# ProPrj__-8777947A-__2025-12-19.net
KiCad netlist of a schematic drawn in EasyEDA Pro
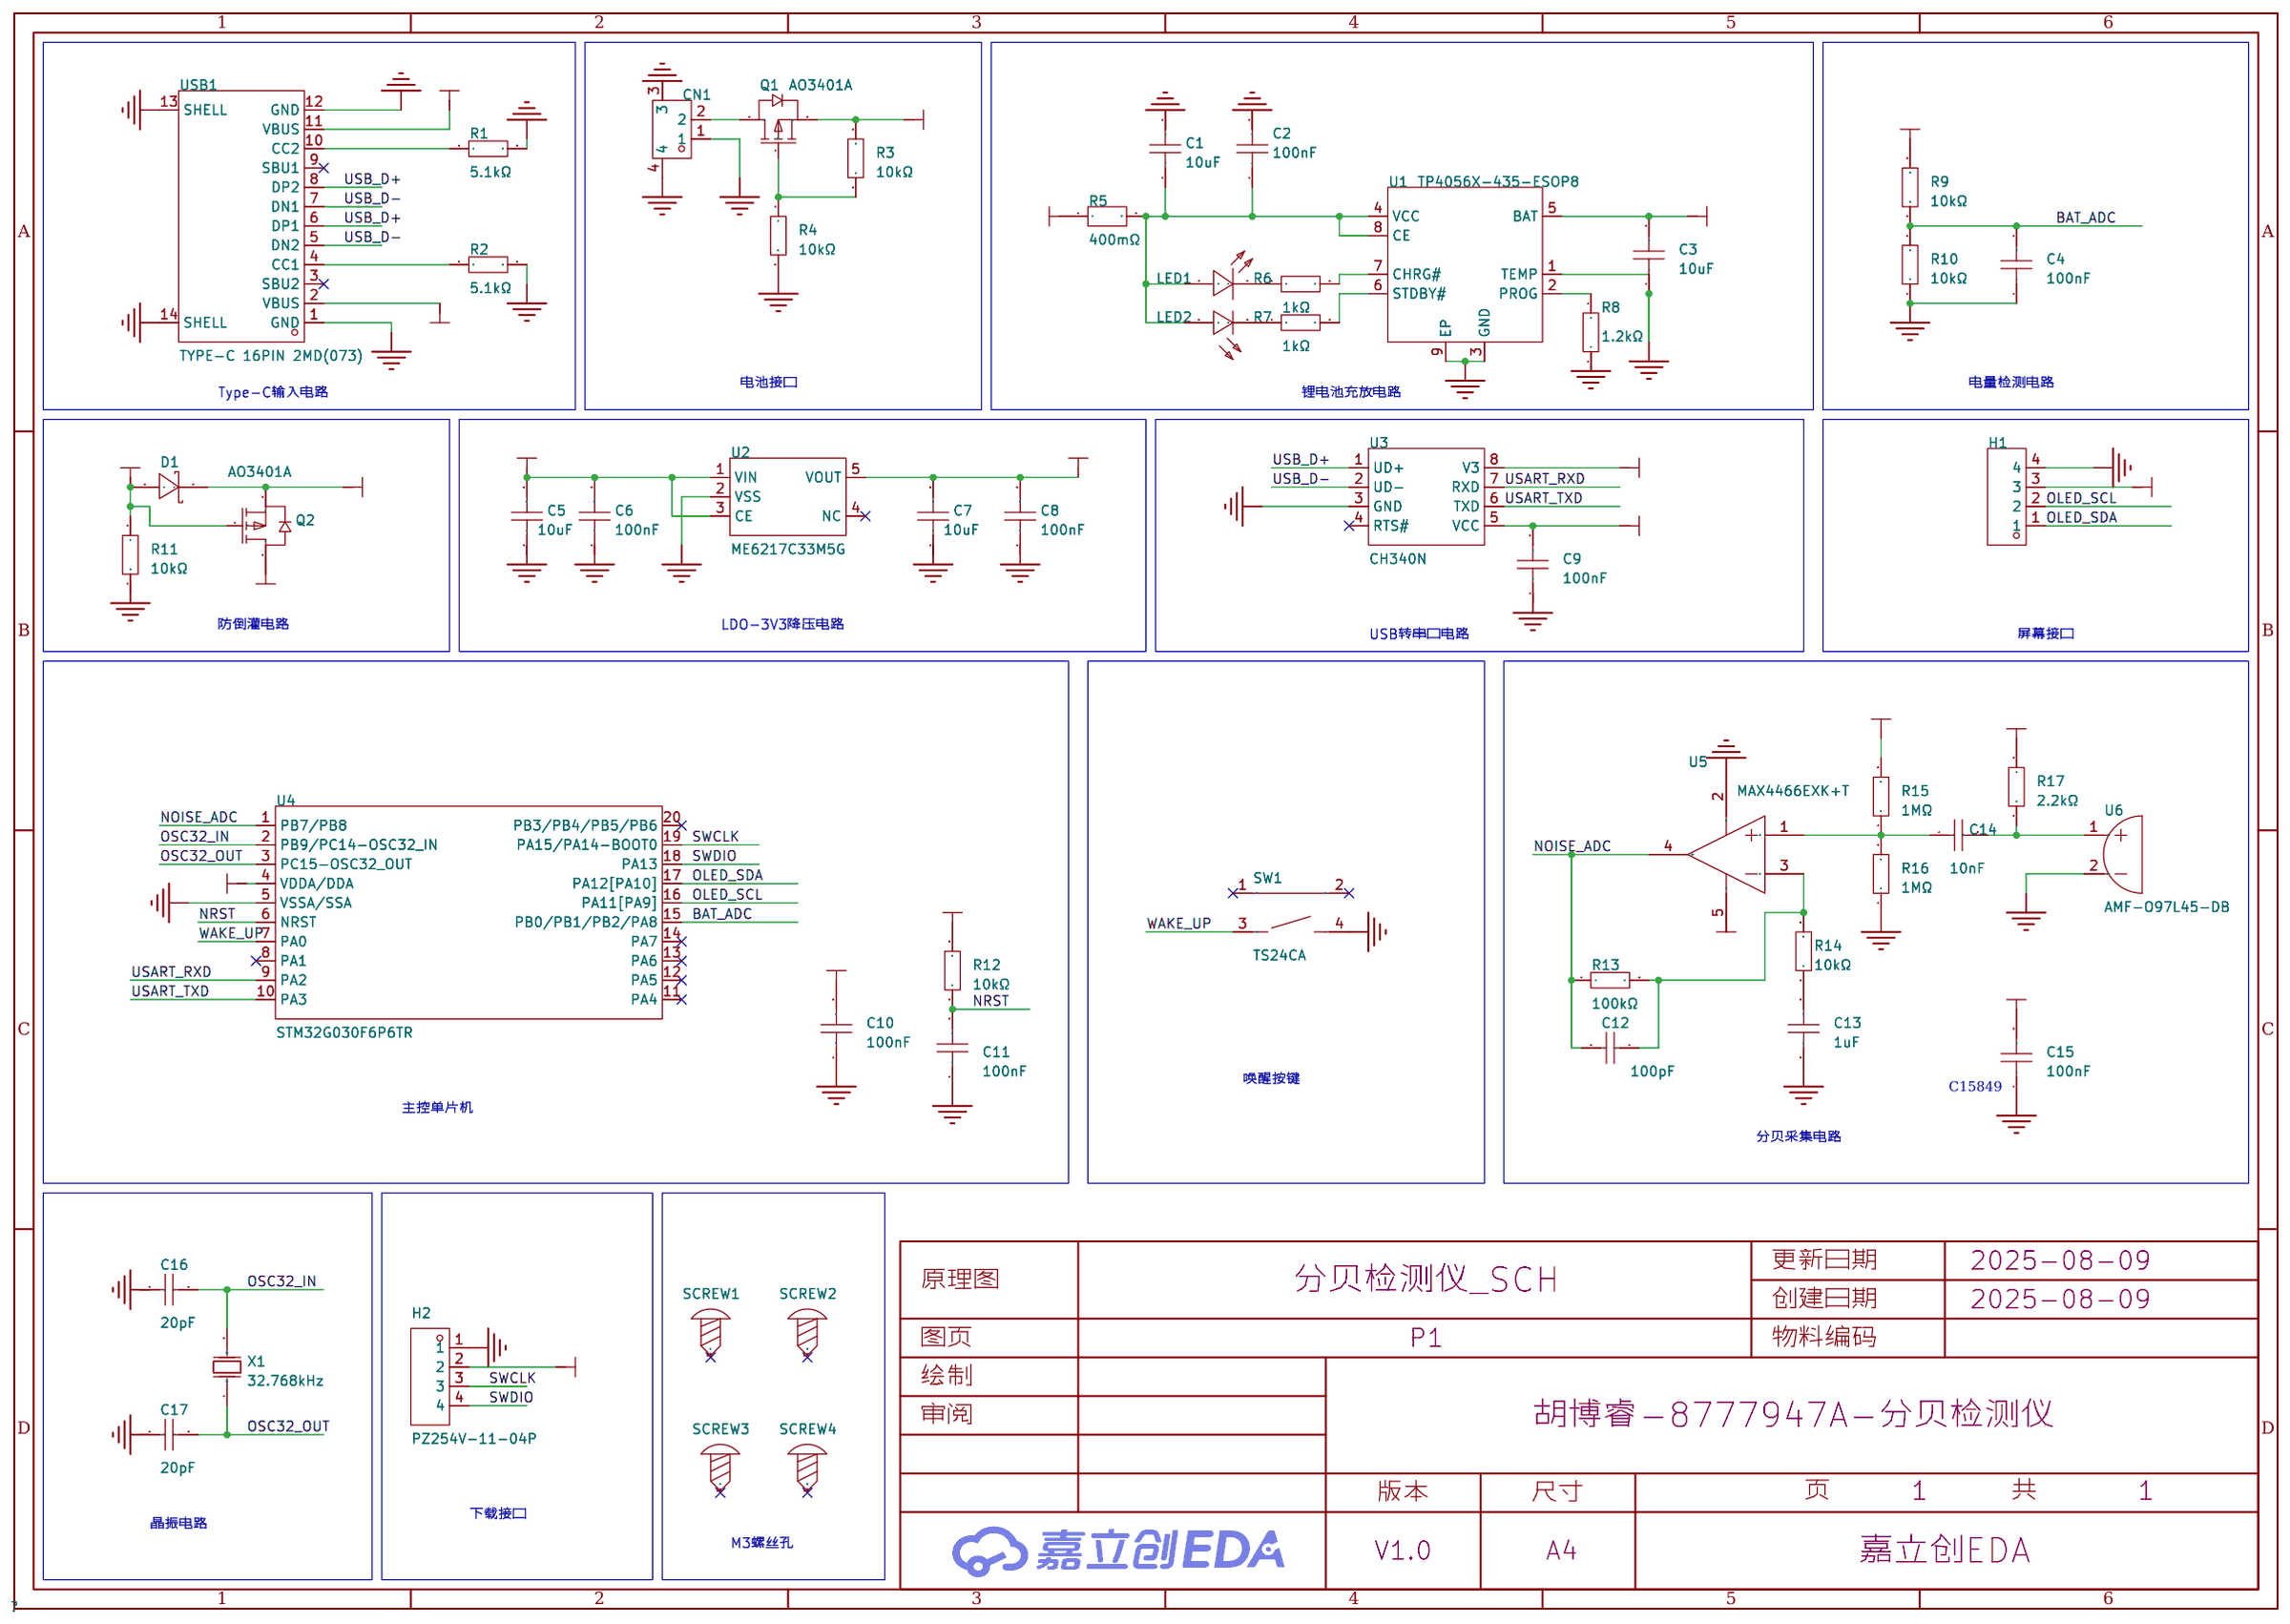
[diagram p0: schematic sheet]

(export (version "E")
  (design (tool "Eeschema 10.0.6"))
  (components
    (comp (ref "C1")
      (value "10uF")
      (footprint "easyedapro:C0805")
      (description "容值:10uF;精度:±10%;额定电压:25V;材质(温度系数):X5R;")
      (fields
        (field (name "Manufacturer Part") "CL21A106KAYNNNE")
        (field (name "Manufacturer") "SAMSUNG(三星)")
      )
      (libsource (lib "easyedapro") (part "CL21A106KAYNNNE"))
    )
    (comp (ref "C2")
      (value "100nF")
      (footprint "easyedapro:C0603")
      (description "容值:100nF;精度:±10%;额定电压:50V;温度系数:X7R;")
      (fields
        (field (name "Manufacturer Part") "CC0603KRX7R9BB104")
        (field (name "Manufacturer") "YAGEO(国巨)")
      )
      (libsource (lib "easyedapro") (part "CC0603KRX7R9BB104"))
    )
    (comp (ref "C3")
      (value "10uF")
      (footprint "easyedapro:C0805")
      (description "容值:10uF;精度:±10%;额定电压:25V;材质(温度系数):X5R;")
      (fields
        (field (name "Manufacturer Part") "CL21A106KAYNNNE")
        (field (name "Manufacturer") "SAMSUNG(三星)")
      )
      (libsource (lib "easyedapro") (part "CL21A106KAYNNNE"))
    )
    (comp (ref "C4")
      (value "100nF")
      (footprint "easyedapro:C0603")
      (description "容值:100nF;精度:±10%;额定电压:50V;温度系数:X7R;")
      (fields
        (field (name "Manufacturer Part") "CC0603KRX7R9BB104")
        (field (name "Manufacturer") "YAGEO(国巨)")
      )
      (libsource (lib "easyedapro") (part "CC0603KRX7R9BB104"))
    )
    (comp (ref "C5")
      (value "10uF")
      (footprint "easyedapro:C0805")
      (description "容值:10uF;精度:±10%;额定电压:25V;材质(温度系数):X5R;")
      (fields
        (field (name "Manufacturer Part") "CL21A106KAYNNNE")
        (field (name "Manufacturer") "SAMSUNG(三星)")
      )
      (libsource (lib "easyedapro") (part "CL21A106KAYNNNE"))
    )
    (comp (ref "C6")
      (value "100nF")
      (footprint "easyedapro:C0603")
      (description "容值:100nF;精度:±10%;额定电压:50V;温度系数:X7R;")
      (fields
        (field (name "Manufacturer Part") "CC0603KRX7R9BB104")
        (field (name "Manufacturer") "YAGEO(国巨)")
      )
      (libsource (lib "easyedapro") (part "CC0603KRX7R9BB104"))
    )
    (comp (ref "C7")
      (value "10uF")
      (footprint "easyedapro:C0805")
      (description "容值:10uF;精度:±10%;额定电压:25V;材质(温度系数):X5R;")
      (fields
        (field (name "Manufacturer Part") "CL21A106KAYNNNE")
        (field (name "Manufacturer") "SAMSUNG(三星)")
      )
      (libsource (lib "easyedapro") (part "CL21A106KAYNNNE"))
    )
    (comp (ref "C8")
      (value "100nF")
      (footprint "easyedapro:C0603")
      (description "容值:100nF;精度:±10%;额定电压:50V;温度系数:X7R;")
      (fields
        (field (name "Manufacturer Part") "CC0603KRX7R9BB104")
        (field (name "Manufacturer") "YAGEO(国巨)")
      )
      (libsource (lib "easyedapro") (part "CC0603KRX7R9BB104"))
    )
    (comp (ref "C9")
      (value "100nF")
      (footprint "easyedapro:C0603")
      (description "容值:100nF;精度:±10%;额定电压:50V;温度系数:X7R;")
      (fields
        (field (name "Manufacturer Part") "CC0603KRX7R9BB104")
        (field (name "Manufacturer") "YAGEO(国巨)")
      )
      (libsource (lib "easyedapro") (part "CC0603KRX7R9BB104"))
    )
    (comp (ref "C10")
      (value "100nF")
      (footprint "easyedapro:C0603")
      (description "容值:100nF;精度:±10%;额定电压:50V;温度系数:X7R;")
      (fields
        (field (name "Manufacturer Part") "CC0603KRX7R9BB104")
        (field (name "Manufacturer") "YAGEO(国巨)")
      )
      (libsource (lib "easyedapro") (part "CC0603KRX7R9BB104"))
    )
    (comp (ref "C11")
      (value "100nF")
      (footprint "easyedapro:C0603")
      (description "容值:100nF;精度:±10%;额定电压:50V;温度系数:X7R;")
      (fields
        (field (name "Manufacturer Part") "CC0603KRX7R9BB104")
        (field (name "Manufacturer") "YAGEO(国巨)")
      )
      (libsource (lib "easyedapro") (part "CC0603KRX7R9BB104"))
    )
    (comp (ref "C12")
      (value "100pF")
      (footprint "easyedapro:C0603")
      (description "容值:100pF;精度:±5%;额定电压:50V;材质(温度系数):C0G;")
      (fields
        (field (name "Manufacturer Part") "CL10C101JB8NNNC")
        (field (name "Manufacturer") "SAMSUNG(三星)")
      )
      (libsource (lib "easyedapro") (part "CL10C101JB8NNNC"))
    )
    (comp (ref "C13")
      (value "1uF")
      (footprint "easyedapro:C0603")
      (description "容值:1uF;精度:±10%;额定电压:50V;材质(温度系数):X5R;")
      (fields
        (field (name "Manufacturer Part") "CL10A105KB8NNNC")
        (field (name "Manufacturer") "SAMSUNG(三星)")
      )
      (libsource (lib "easyedapro") (part "CL10A105KB8NNNC"))
    )
    (comp (ref "C14")
      (value "10nF")
      (footprint "easyedapro:C0603")
      (description "容值:10nF;精度:±10%;额定电压:50V;温度系数:X7R;")
      (fields (field (name "Manufacturer Part") "0603B103K500NT") (field (name "Manufacturer") "FH(风华)"))
      (libsource (lib "easyedapro") (part "0603B103K500NT"))
    )
    (comp (ref "C15")
      (value "100nF")
      (footprint "easyedapro:C0603")
      (description "容值:100nF;精度:±10%;额定电压:50V;温度系数:X7R;")
      (fields
        (field (name "Manufacturer Part") "CC0603KRX7R9BB104")
        (field (name "Manufacturer") "YAGEO(国巨)")
      )
      (libsource (lib "easyedapro") (part "CC0603KRX7R9BB104"))
    )
    (comp (ref "C16")
      (value "20pF")
      (footprint "easyedapro:C0603")
      (description "容值:20pF;精度:±5%;额定电压:50V;材质(温度系数):C0G;")
      (fields
        (field (name "Manufacturer Part") "CL10C200JB8NNNC")
        (field (name "Manufacturer") "SAMSUNG(三星)")
      )
      (libsource (lib "easyedapro") (part "CL10C200JB8NNNC"))
    )
    (comp (ref "C17")
      (value "20pF")
      (footprint "easyedapro:C0603")
      (description "容值:20pF;精度:±5%;额定电压:50V;材质(温度系数):C0G;")
      (fields
        (field (name "Manufacturer Part") "CL10C200JB8NNNC")
        (field (name "Manufacturer") "SAMSUNG(三星)")
      )
      (libsource (lib "easyedapro") (part "CL10C200JB8NNNC"))
    )
    (comp (ref "CN1")
      (value "WAFER-254W-2A")
      (footprint "easyedapro:CONN-SMD_2P-L10.0-W7.8-P2.5")
      (description "插针结构:1x2P;间距:2.54mm;安装方式:卧贴;参考系列:XH;总PIN数:2P;排数:1;每排PIN数:2;行距:-;额定电流:3A;工作温度:-25°C~+85°C;")
      (fields (field (name "Manufacturer") "HANBO(汉博)"))
      (libsource (lib "easyedapro") (part "WAFER-254W-2A"))
    )
    (comp (ref "D1")
      (value "1N5819WS")
      (footprint "easyedapro:SOD-323_L1.8-W1.3-LS2.5-RD")
      (description "正向压降(Vf):600mV@1A;直流反向耐压(Vr):40V;整流电流:1A;")
      (fields (field (name "Manufacturer") "Hottech(合科泰)"))
      (libsource (lib "easyedapro") (part "1N5819WS"))
    )
    (comp (ref "H1")
      (value "2.54-1*4P母")
      (footprint "easyedapro:HDR-TH_4P-P2.54-V-F")
      (fields (field (name "Manufacturer") "BOOMELE(博穆精密)"))
      (libsource (lib "easyedapro") (part "2.54-1*4P母"))
    )
    (comp (ref "H2")
      (value "PZ254V-11-04P")
      (footprint "easyedapro:HDR-TH_4P-P2.54-V-M")
      (fields (field (name "Manufacturer") "XFCN(兴飞)"))
      (libsource (lib "easyedapro") (part "PZ254V-11-04P_C2691448"))
    )
    (comp (ref "LED1")
      (value "KT-0603R")
      (footprint "easyedapro:LED0603-RD")
      (description "发光颜色:红色;功率:-;正向电流:-;主波长:-;二极管配置:-;透镜颜色:-;色温:-;发光角度:-;载带方式:-;工作温度:-40°C~+85°C;")
      (fields (field (name "Manufacturer") "KENTO"))
      (libsource (lib "easyedapro") (part "KT-0603R"))
    )
    (comp (ref "LED2")
      (value "NCD0603G1")
      (footprint "easyedapro:LED0603-RD_1")
      (fields (field (name "Manufacturer") "国星光电"))
      (libsource (lib "easyedapro") (part "FC-D1608UGK-520D10"))
    )
    (comp (ref "Q1")
      (value "AO3401A")
      (footprint "easyedapro:SOT-23_L2.9-W1.3-P1.90-LS2.4-BR")
      (fields (field (name "Manufacturer") "UMW(友台半导体)"))
      (libsource (lib "easyedapro") (part "AO3401A_C347476"))
    )
    (comp (ref "Q2")
      (value "AO3401A")
      (footprint "easyedapro:SOT-23_L2.9-W1.3-P1.90-LS2.4-BR")
      (fields (field (name "Manufacturer") "UMW(友台半导体)"))
      (libsource (lib "easyedapro") (part "AO3401A_C347476"))
    )
    (comp (ref "R1")
      (value "5.1kΩ")
      (footprint "easyedapro:R0603")
      (description "电阻类型:厚膜电阻;阻值:5.1kΩ;精度:±1%;功率:100mW;工作电压:75V;温度系数:±100ppm/°C;")
      (fields
        (field (name "Manufacturer Part") "0603WAF5101T5E")
        (field (name "Manufacturer") "UNI-ROYAL(厚声)")
      )
      (libsource (lib "easyedapro") (part "0603WAF5101T5E"))
    )
    (comp (ref "R2")
      (value "5.1kΩ")
      (footprint "easyedapro:R0603")
      (description "电阻类型:厚膜电阻;阻值:5.1kΩ;精度:±1%;功率:100mW;工作电压:75V;温度系数:±100ppm/°C;")
      (fields
        (field (name "Manufacturer Part") "0603WAF5101T5E")
        (field (name "Manufacturer") "UNI-ROYAL(厚声)")
      )
      (libsource (lib "easyedapro") (part "0603WAF5101T5E"))
    )
    (comp (ref "R3")
      (value "10kΩ")
      (footprint "easyedapro:R0603")
      (description "电阻类型:厚膜电阻;阻值:10kΩ;精度:±1%;功率:100mW;工作电压:75V;温度系数:±100ppm/°C;")
      (fields
        (field (name "Manufacturer Part") "0603WAF1002T5E")
        (field (name "Manufacturer") "UNI-ROYAL(厚声)")
      )
      (libsource (lib "easyedapro") (part "0603WAF1002T5E"))
    )
    (comp (ref "R4")
      (value "10kΩ")
      (footprint "easyedapro:R0603")
      (description "电阻类型:厚膜电阻;阻值:10kΩ;精度:±1%;功率:100mW;工作电压:75V;温度系数:±100ppm/°C;")
      (fields
        (field (name "Manufacturer Part") "0603WAF1002T5E")
        (field (name "Manufacturer") "UNI-ROYAL(厚声)")
      )
      (libsource (lib "easyedapro") (part "0603WAF1002T5E"))
    )
    (comp (ref "R5")
      (value "400mΩ")
      (footprint "easyedapro:R1206")
      (description "电阻类型:厚膜电阻;阻值:400mΩ;精度:±1%;功率:250mW;最大工作电压:500V;温度系数:±300ppm/°C;")
      (fields (field (name "Manufacturer Part") "FRL1206FR400TS") (field (name "Manufacturer") "FOJAN(富捷)"))
      (libsource (lib "easyedapro") (part "FRL1206FR400TS"))
    )
    (comp (ref "R6")
      (value "1kΩ")
      (footprint "easyedapro:R0603")
      (description "电阻类型:厚膜电阻;阻值:1kΩ;精度:±1%;功率:100mW;最大工作电压:75V;温度系数:±100ppm/°C;")
      (fields
        (field (name "Manufacturer Part") "0603WAF1001T5E")
        (field (name "Manufacturer") "UNI-ROYAL(厚声)")
      )
      (libsource (lib "easyedapro") (part "0603WAF1001T5E"))
    )
    (comp (ref "R7")
      (value "1kΩ")
      (footprint "easyedapro:R0603")
      (description "电阻类型:厚膜电阻;阻值:1kΩ;精度:±1%;功率:100mW;最大工作电压:75V;温度系数:±100ppm/°C;")
      (fields
        (field (name "Manufacturer Part") "0603WAF1001T5E")
        (field (name "Manufacturer") "UNI-ROYAL(厚声)")
      )
      (libsource (lib "easyedapro") (part "0603WAF1001T5E"))
    )
    (comp (ref "R8")
      (value "1.2kΩ")
      (footprint "easyedapro:R0603")
      (description "电阻类型:厚膜电阻;阻值:1.2kΩ;精度:±1%;功率:100mW;最大工作电压:75V;温度系数:±100ppm/°C;")
      (fields
        (field (name "Manufacturer Part") "0603WAF1201T5E")
        (field (name "Manufacturer") "UNI-ROYAL(厚声)")
      )
      (libsource (lib "easyedapro") (part "0603WAF1201T5E"))
    )
    (comp (ref "R9")
      (value "10kΩ")
      (footprint "easyedapro:R0603")
      (description "电阻类型:厚膜电阻;阻值:10kΩ;精度:±1%;功率:100mW;工作电压:75V;温度系数:±100ppm/°C;")
      (fields
        (field (name "Manufacturer Part") "0603WAF1002T5E")
        (field (name "Manufacturer") "UNI-ROYAL(厚声)")
      )
      (libsource (lib "easyedapro") (part "0603WAF1002T5E"))
    )
    (comp (ref "R10")
      (value "10kΩ")
      (footprint "easyedapro:R0603")
      (description "电阻类型:厚膜电阻;阻值:10kΩ;精度:±1%;功率:100mW;工作电压:75V;温度系数:±100ppm/°C;")
      (fields
        (field (name "Manufacturer Part") "0603WAF1002T5E")
        (field (name "Manufacturer") "UNI-ROYAL(厚声)")
      )
      (libsource (lib "easyedapro") (part "0603WAF1002T5E"))
    )
    (comp (ref "R11")
      (value "10kΩ")
      (footprint "easyedapro:R0603")
      (description "电阻类型:厚膜电阻;阻值:10kΩ;精度:±1%;功率:100mW;工作电压:75V;温度系数:±100ppm/°C;")
      (fields
        (field (name "Manufacturer Part") "0603WAF1002T5E")
        (field (name "Manufacturer") "UNI-ROYAL(厚声)")
      )
      (libsource (lib "easyedapro") (part "0603WAF1002T5E"))
    )
    (comp (ref "R12")
      (value "10kΩ")
      (footprint "easyedapro:R0603")
      (description "电阻类型:厚膜电阻;阻值:10kΩ;精度:±1%;功率:100mW;工作电压:75V;温度系数:±100ppm/°C;")
      (fields
        (field (name "Manufacturer Part") "0603WAF1002T5E")
        (field (name "Manufacturer") "UNI-ROYAL(厚声)")
      )
      (libsource (lib "easyedapro") (part "0603WAF1002T5E"))
    )
    (comp (ref "R13")
      (value "100kΩ")
      (footprint "easyedapro:R0603")
      (description "电阻类型:厚膜电阻;阻值:100kΩ;精度:±1%;功率:100mW;最大工作电压:75V;温度系数:±100ppm/°C;")
      (fields
        (field (name "Manufacturer Part") "0603WAF1003T5E")
        (field (name "Manufacturer") "UNI-ROYAL(厚声)")
      )
      (libsource (lib "easyedapro") (part "0603WAF1003T5E"))
    )
    (comp (ref "R14")
      (value "10kΩ")
      (footprint "easyedapro:R0603")
      (description "电阻类型:厚膜电阻;阻值:10kΩ;精度:±1%;功率:100mW;工作电压:75V;温度系数:±100ppm/°C;")
      (fields
        (field (name "Manufacturer Part") "0603WAF1002T5E")
        (field (name "Manufacturer") "UNI-ROYAL(厚声)")
      )
      (libsource (lib "easyedapro") (part "0603WAF1002T5E"))
    )
    (comp (ref "R15")
      (value "1MΩ")
      (footprint "easyedapro:R0603")
      (description "电阻类型:厚膜电阻;阻值:1MΩ;精度:±1%;功率:100mW;最大工作电压:75V;温度系数:±100ppm/°C;")
      (fields
        (field (name "Manufacturer Part") "0603WAF1004T5E")
        (field (name "Manufacturer") "UNI-ROYAL(厚声)")
      )
      (libsource (lib "easyedapro") (part "0603WAF1004T5E"))
    )
    (comp (ref "R16")
      (value "1MΩ")
      (footprint "easyedapro:R0603")
      (description "电阻类型:厚膜电阻;阻值:1MΩ;精度:±1%;功率:100mW;最大工作电压:75V;温度系数:±100ppm/°C;")
      (fields
        (field (name "Manufacturer Part") "0603WAF1004T5E")
        (field (name "Manufacturer") "UNI-ROYAL(厚声)")
      )
      (libsource (lib "easyedapro") (part "0603WAF1004T5E"))
    )
    (comp (ref "R17")
      (value "2.2kΩ")
      (footprint "easyedapro:R0603")
      (description "电阻类型:厚膜电阻;阻值:2.2kΩ;精度:±1%;功率:100mW;最大工作电压:75V;温度系数:±100ppm/°C;")
      (fields
        (field (name "Manufacturer Part") "0603WAF2201T5E")
        (field (name "Manufacturer") "UNI-ROYAL(厚声)")
      )
      (libsource (lib "easyedapro") (part "0603WAF2201T5E"))
    )
    (comp (ref "SCREW1")
      (value "~")
      (footprint "easyedapro:M3螺丝")
      (libsource (lib "easyedapro") (part "螺丝孔"))
    )
    (comp (ref "SCREW2")
      (value "~")
      (footprint "easyedapro:M3螺丝")
      (libsource (lib "easyedapro") (part "螺丝孔"))
    )
    (comp (ref "SCREW3")
      (value "~")
      (footprint "easyedapro:M3螺丝")
      (libsource (lib "easyedapro") (part "螺丝孔"))
    )
    (comp (ref "SCREW4")
      (value "~")
      (footprint "easyedapro:M3螺丝")
      (libsource (lib "easyedapro") (part "螺丝孔"))
    )
    (comp (ref "SW1")
      (value "TS24CA")
      (footprint "easyedapro:SW-SMD_TS24CA")
      (description "电路结构:单刀单掷;按钮形状:矩形按钮;安装方式:卧贴;开关长度:4.55mm;开关宽度:1.8mm;开关高度:3.5mm;触点电流:50mA;额定电压:12V;带灯:-;工作寿命:-;")
      (fields (field (name "Manufacturer") "SHOU HAN(首韩)"))
      (libsource (lib "easyedapro") (part "TS24CA"))
    )
    (comp (ref "U1")
      (value "TP4056X-435-ESOP8")
      (footprint "easyedapro:ESOP-8_L4.9-W3.9-P1.27-LS6.0-BL-EP")
      (fields (field (name "Manufacturer") "TOPPOWER(南京拓微)"))
      (libsource (lib "easyedapro") (part "TP4056X-435-ESOP8"))
    )
    (comp (ref "U2")
      (value "ME6217C33M5G")
      (footprint "easyedapro:SOT-23-5_L3.0-W1.7-P0.95-LS2.8-BR")
      (description "输出类型:固定;工作电压:6.5V;输出电压:3.3V;输出电流:800mA;电源纹波抑制比(PSRR):65dB@(1kHz);输出极性:正极;")
      (fields (field (name "Manufacturer") "MICRONE(南京微盟)"))
      (libsource (lib "easyedapro") (part "ME6217C33M5G"))
    )
    (comp (ref "U3")
      (value "CH340N")
      (footprint "easyedapro:SOP-8_L4.9-W3.9-P1.27-LS6.0-BL")
      (description "应用功能:USB转串口;接口协议:USB 2.0;通道数:1;数据速率:2Mbps;")
      (fields (field (name "Manufacturer") "WCH(南京沁恒)"))
      (libsource (lib "easyedapro") (part "CH340N_C2977777"))
    )
    (comp (ref "U4")
      (value "STM32G030F6P6TR")
      (footprint "easyedapro:TSSOP-20_L6.5-W4.4-P0.65-LS6.4-BL")
      (description "CPU内核:-;CPU最大主频:64MHz;")
      (fields (field (name "Manufacturer") "ST(意法半导体)"))
      (libsource (lib "easyedapro") (part "STM32G030F6P6TR"))
    )
    (comp (ref "U5")
      (value "MAX4466EXK+T")
      (footprint "easyedapro:SC-70-5_L2.0-W1.3-P0.65-LS2.1-BR")
      (description "功放类型:-;扬声器通道数:单声道;输出功率:-;静态电流(Iq):-;")
      (fields (field (name "Manufacturer") "ADI(亚德诺)/MAXIM(美信)"))
      (libsource (lib "easyedapro") (part "MAX4466EXK+T"))
    )
    (comp (ref "U6")
      (value "AMF-O97L45-DB")
      (footprint "easyedapro:MIC-TH_BD9.7-P2.50-D0.8-L-FD")
      (description "指向性:全指向;输出阻抗:2.2kΩ;信噪比:58dB;灵敏度:-45dB@±3dB;")
      (fields (field (name "Manufacturer") "Dragonstate(华龙)"))
      (libsource (lib "easyedapro") (part "AMF-O97L45-DB"))
    )
    (comp (ref "USB1")
      (value "TYPE-C 16PIN 2MD(073)")
      (footprint "easyedapro:USB-C-SMD_TYPE-C-6PIN-2MD-073")
      (description "连接器类型:Type-C;协议标准:USB 3.1;公母:母;安装方式:卧贴;触点数量:16P;端口数量:1;额定电流 - 电源:3A;工作温度:-25°C~+85°C;")
      (fields (field (name "Manufacturer") "SHOU HAN(首韩)"))
      (libsource (lib "easyedapro") (part "TYPE-C 16PIN 2MD(073)"))
    )
    (comp (ref "X1")
      (value "32.768kHz")
      (footprint "easyedapro:CRYSTAL-SMD_L3.2-W1.5-1")
      (description "晶振类型:贴片晶振;频率:32.768kHz;常温频差:±20ppm;负载电容:12.5pF;频率稳定度:±30ppm;")
      (fields
        (field (name "Manufacturer Part") "XKXGI-SUA-32.768K")
        (field (name "Manufacturer") "YXC(扬兴晶振)")
      )
      (libsource (lib "easyedapro") (part "XKXGI-SUA-32.768K"))
    )
  )
  (nets
    (net (code "1") (name "+3V3") (class "Default")
      (node (ref "C10") (pin "2") (pinfunction "2_2") (pintype "unspecified"))
      (node (ref "C15") (pin "2") (pinfunction "2_2") (pintype "unspecified"))
      (node (ref "C7") (pin "2") (pinfunction "2_2") (pintype "unspecified"))
      (node (ref "C8") (pin "2") (pinfunction "2_2") (pintype "unspecified"))
      (node (ref "C9") (pin "2") (pinfunction "2_2") (pintype "unspecified"))
      (node (ref "H1") (pin "3") (pinfunction "3_3") (pintype "unspecified"))
      (node (ref "H2") (pin "2") (pinfunction "2_2") (pintype "unspecified"))
      (node (ref "R12") (pin "2") (pinfunction "2_2") (pintype "input"))
      (node (ref "R15") (pin "2") (pinfunction "2_2") (pintype "input"))
      (node (ref "R17") (pin "2") (pinfunction "2_2") (pintype "input"))
      (node (ref "U2") (pin "5") (pinfunction "VOUT_5") (pintype "unspecified"))
      (node (ref "U3") (pin "5") (pinfunction "VCC_5") (pintype "unspecified"))
      (node (ref "U3") (pin "8") (pinfunction "V3_8") (pintype "unspecified"))
      (node (ref "U4") (pin "4") (pinfunction "VDDA/DDA_4") (pintype "unspecified"))
      (node (ref "U5") (pin "5") (pinfunction "VCC_5") (pintype "unspecified"))
    )
    (net (code "2") (name "/BAT_ADC") (class "Default")
      (node (ref "C4") (pin "2") (pinfunction "2_2") (pintype "unspecified"))
      (node (ref "R10") (pin "2") (pinfunction "2_2") (pintype "input"))
      (node (ref "R9") (pin "1") (pinfunction "1_1") (pintype "input"))
      (node (ref "U4") (pin "15") (pinfunction "PB0/PB1/PB2/PA8_15") (pintype "unspecified"))
    )
    (net (code "3") (name "/NOISE_ADC") (class "Default")
      (node (ref "C12") (pin "2") (pinfunction "2_2") (pintype "input"))
      (node (ref "R13") (pin "1") (pinfunction "1_1") (pintype "input"))
      (node (ref "U4") (pin "1") (pinfunction "PB7/PB8_1") (pintype "unspecified"))
      (node (ref "U5") (pin "4") (pinfunction "OUT_4") (pintype "output"))
    )
    (net (code "4") (name "/NRST") (class "Default")
      (node (ref "C11") (pin "2") (pinfunction "2_2") (pintype "unspecified"))
      (node (ref "R12") (pin "1") (pinfunction "1_1") (pintype "input"))
      (node (ref "U4") (pin "6") (pinfunction "NRST_6") (pintype "unspecified"))
    )
    (net (code "5") (name "/OLED_SCL") (class "Default")
      (node (ref "H1") (pin "2") (pinfunction "2_2") (pintype "unspecified"))
      (node (ref "U4") (pin "16") (pinfunction "PA11[PA9]_16") (pintype "unspecified"))
    )
    (net (code "6") (name "/OLED_SDA") (class "Default")
      (node (ref "H1") (pin "1") (pinfunction "1_1") (pintype "unspecified"))
      (node (ref "U4") (pin "17") (pinfunction "PA12[PA10]_17") (pintype "unspecified"))
    )
    (net (code "7") (name "/OSC32_IN") (class "Default")
      (node (ref "C16") (pin "2") (pinfunction "2_2") (pintype "input"))
      (node (ref "U4") (pin "2") (pinfunction "PB9/PC14-OSC32_IN_2") (pintype "unspecified"))
      (node (ref "X1") (pin "2") (pinfunction "OSC2_2") (pintype "input"))
    )
    (net (code "8") (name "/OSC32_OUT") (class "Default")
      (node (ref "C17") (pin "2") (pinfunction "2_2") (pintype "input"))
      (node (ref "U4") (pin "3") (pinfunction "PC15-OSC32_OUT_3") (pintype "unspecified"))
      (node (ref "X1") (pin "1") (pinfunction "OSC1_1") (pintype "input"))
    )
    (net (code "9") (name "/SWCLK") (class "Default")
      (node (ref "H2") (pin "3") (pinfunction "3_3") (pintype "unspecified"))
      (node (ref "U4") (pin "19") (pinfunction "PA15/PA14-BOOT0_19") (pintype "unspecified"))
    )
    (net (code "10") (name "/SWDIO") (class "Default")
      (node (ref "H2") (pin "4") (pinfunction "4_4") (pintype "unspecified"))
      (node (ref "U4") (pin "18") (pinfunction "PA13_18") (pintype "unspecified"))
    )
    (net (code "11") (name "/USART_RXD") (class "Default")
      (node (ref "U3") (pin "7") (pinfunction "RXD_7") (pintype "unspecified"))
      (node (ref "U4") (pin "9") (pinfunction "PA2_9") (pintype "unspecified"))
    )
    (net (code "12") (name "/USART_TXD") (class "Default")
      (node (ref "U3") (pin "6") (pinfunction "TXD_6") (pintype "unspecified"))
      (node (ref "U4") (pin "10") (pinfunction "PA3_10") (pintype "unspecified"))
    )
    (net (code "13") (name "/USB_D+") (class "Default")
      (node (ref "U3") (pin "1") (pinfunction "UD+_1") (pintype "unspecified"))
      (node (ref "USB1") (pin "6") (pinfunction "DP1_6") (pintype "unspecified"))
      (node (ref "USB1") (pin "8") (pinfunction "DP2_8") (pintype "unspecified"))
    )
    (net (code "14") (name "/USB_D-") (class "Default")
      (node (ref "U3") (pin "2") (pinfunction "UD-_2") (pintype "unspecified"))
      (node (ref "USB1") (pin "5") (pinfunction "DN2_5") (pintype "unspecified"))
      (node (ref "USB1") (pin "7") (pinfunction "DN1_7") (pintype "unspecified"))
    )
    (net (code "15") (name "/WAKE_UP") (class "Default")
      (node (ref "SW1") (pin "3") (pinfunction "3_3") (pintype "unspecified"))
      (node (ref "U4") (pin "7") (pinfunction "PA0_7") (pintype "unspecified"))
    )
    (net (code "16") (name "BAT+") (class "Default")
      (node (ref "C3") (pin "2") (pinfunction "2_2") (pintype "unspecified"))
      (node (ref "Q1") (pin "2") (pinfunction "S_2") (pintype "unspecified"))
      (node (ref "Q2") (pin "3") (pinfunction "D_3") (pintype "unspecified"))
      (node (ref "R3") (pin "2") (pinfunction "2_2") (pintype "input"))
      (node (ref "R9") (pin "2") (pinfunction "2_2") (pintype "input"))
      (node (ref "U1") (pin "5") (pinfunction "BAT_5") (pintype "unspecified"))
    )
    (net (code "17") (name "GND") (class "Default")
      (node (ref "C1") (pin "2") (pinfunction "2_2") (pintype "unspecified"))
      (node (ref "C10") (pin "1") (pinfunction "1_1") (pintype "unspecified"))
      (node (ref "C11") (pin "1") (pinfunction "1_1") (pintype "unspecified"))
      (node (ref "C13") (pin "1") (pinfunction "1_1") (pintype "unspecified"))
      (node (ref "C15") (pin "1") (pinfunction "1_1") (pintype "unspecified"))
      (node (ref "C16") (pin "1") (pinfunction "1_1") (pintype "input"))
      (node (ref "C17") (pin "1") (pinfunction "1_1") (pintype "input"))
      (node (ref "C2") (pin "2") (pinfunction "2_2") (pintype "unspecified"))
      (node (ref "C3") (pin "1") (pinfunction "1_1") (pintype "unspecified"))
      (node (ref "C4") (pin "1") (pinfunction "1_1") (pintype "unspecified"))
      (node (ref "C5") (pin "1") (pinfunction "1_1") (pintype "unspecified"))
      (node (ref "C6") (pin "1") (pinfunction "1_1") (pintype "unspecified"))
      (node (ref "C7") (pin "1") (pinfunction "1_1") (pintype "unspecified"))
      (node (ref "C8") (pin "1") (pinfunction "1_1") (pintype "unspecified"))
      (node (ref "C9") (pin "1") (pinfunction "1_1") (pintype "unspecified"))
      (node (ref "CN1") (pin "1") (pinfunction "1_1") (pintype "unspecified"))
      (node (ref "CN1") (pin "3") (pinfunction "3_3") (pintype "unspecified"))
      (node (ref "CN1") (pin "4") (pinfunction "4_4") (pintype "unspecified"))
      (node (ref "H1") (pin "4") (pinfunction "4_4") (pintype "unspecified"))
      (node (ref "H2") (pin "1") (pinfunction "1_1") (pintype "unspecified"))
      (node (ref "R1") (pin "2") (pinfunction "2_2") (pintype "input"))
      (node (ref "R10") (pin "1") (pinfunction "1_1") (pintype "input"))
      (node (ref "R11") (pin "1") (pinfunction "1_1") (pintype "input"))
      (node (ref "R16") (pin "1") (pinfunction "1_1") (pintype "input"))
      (node (ref "R2") (pin "2") (pinfunction "2_2") (pintype "input"))
      (node (ref "R4") (pin "2") (pinfunction "2_2") (pintype "input"))
      (node (ref "R8") (pin "1") (pinfunction "1_1") (pintype "input"))
      (node (ref "SW1") (pin "4") (pinfunction "4_4") (pintype "unspecified"))
      (node (ref "U1") (pin "1") (pinfunction "TEMP_1") (pintype "unspecified"))
      (node (ref "U1") (pin "3") (pinfunction "GND_3") (pintype "unspecified"))
      (node (ref "U1") (pin "9") (pinfunction "EP_9") (pintype "unspecified"))
      (node (ref "U2") (pin "2") (pinfunction "VSS_2") (pintype "unspecified"))
      (node (ref "U3") (pin "3") (pinfunction "GND_3") (pintype "unspecified"))
      (node (ref "U4") (pin "5") (pinfunction "VSSA/SSA_5") (pintype "unspecified"))
      (node (ref "U5") (pin "2") (pinfunction "GND_2") (pintype "unspecified"))
      (node (ref "U6") (pin "2") (pinfunction "2_2") (pintype "unspecified"))
      (node (ref "USB1") (pin "1") (pinfunction "GND_1") (pintype "unspecified"))
      (node (ref "USB1") (pin "12") (pinfunction "GND_12") (pintype "unspecified"))
      (node (ref "USB1") (pin "13") (pinfunction "SHELL_13") (pintype "unspecified"))
      (node (ref "USB1") (pin "14") (pinfunction "SHELL_14") (pintype "unspecified"))
    )
    (net (code "18") (name "Net-(C13-Pad2)") (class "Default")
      (node (ref "C13") (pin "2") (pinfunction "2_2") (pintype "unspecified"))
      (node (ref "R14") (pin "1") (pinfunction "1_1") (pintype "input"))
    )
    (net (code "19") (name "Net-(C14-Pad2)") (class "Default")
      (node (ref "C14") (pin "2") (pinfunction "2_2") (pintype "input"))
      (node (ref "R17") (pin "1") (pinfunction "1_1") (pintype "input"))
      (node (ref "U6") (pin "1") (pinfunction "1_1") (pintype "unspecified"))
    )
    (net (code "20") (name "Net-(LED1-A)") (class "Default")
      (node (ref "C1") (pin "1") (pinfunction "1_1") (pintype "unspecified"))
      (node (ref "C2") (pin "1") (pinfunction "1_1") (pintype "unspecified"))
      (node (ref "LED1") (pin "2") (pinfunction "A_2") (pintype "unspecified"))
      (node (ref "LED2") (pin "2") (pinfunction "A_2") (pintype "input"))
      (node (ref "R5") (pin "2") (pinfunction "2_2") (pintype "unspecified"))
      (node (ref "U1") (pin "4") (pinfunction "VCC_4") (pintype "unspecified"))
      (node (ref "U1") (pin "8") (pinfunction "CE_8") (pintype "unspecified"))
    )
    (net (code "21") (name "Net-(LED1-K)") (class "Default")
      (node (ref "LED1") (pin "1") (pinfunction "K_1") (pintype "unspecified"))
      (node (ref "R6") (pin "1") (pinfunction "1_1") (pintype "input"))
    )
    (net (code "22") (name "Net-(LED2-K)") (class "Default")
      (node (ref "LED2") (pin "1") (pinfunction "K_1") (pintype "input"))
      (node (ref "R7") (pin "1") (pinfunction "1_1") (pintype "input"))
    )
    (net (code "23") (name "Net-(Q1-D)") (class "Default")
      (node (ref "CN1") (pin "2") (pinfunction "2_2") (pintype "unspecified"))
      (node (ref "Q1") (pin "3") (pinfunction "D_3") (pintype "unspecified"))
    )
    (net (code "24") (name "Net-(Q1-G)") (class "Default")
      (node (ref "Q1") (pin "1") (pinfunction "G_1") (pintype "unspecified"))
      (node (ref "R3") (pin "1") (pinfunction "1_1") (pintype "input"))
      (node (ref "R4") (pin "1") (pinfunction "1_1") (pintype "input"))
    )
    (net (code "25") (name "Net-(U1-CHRG#)") (class "Default")
      (node (ref "R6") (pin "2") (pinfunction "2_2") (pintype "input"))
      (node (ref "U1") (pin "7") (pinfunction "CHRG#_7") (pintype "unspecified"))
    )
    (net (code "26") (name "Net-(U1-PROG)") (class "Default")
      (node (ref "R8") (pin "2") (pinfunction "2_2") (pintype "input"))
      (node (ref "U1") (pin "2") (pinfunction "PROG_2") (pintype "unspecified"))
    )
    (net (code "27") (name "Net-(U1-STDBY#)") (class "Default")
      (node (ref "R7") (pin "2") (pinfunction "2_2") (pintype "input"))
      (node (ref "U1") (pin "6") (pinfunction "STDBY#_6") (pintype "unspecified"))
    )
    (net (code "28") (name "Net-(U5-IN+)") (class "Default")
      (node (ref "C14") (pin "1") (pinfunction "1_1") (pintype "input"))
      (node (ref "R15") (pin "1") (pinfunction "1_1") (pintype "input"))
      (node (ref "R16") (pin "2") (pinfunction "2_2") (pintype "input"))
      (node (ref "U5") (pin "1") (pinfunction "IN+_1") (pintype "unspecified"))
    )
    (net (code "29") (name "Net-(U5-IN-)") (class "Default")
      (node (ref "C12") (pin "1") (pinfunction "1_1") (pintype "input"))
      (node (ref "R13") (pin "2") (pinfunction "2_2") (pintype "input"))
      (node (ref "R14") (pin "2") (pinfunction "2_2") (pintype "input"))
      (node (ref "U5") (pin "3") (pinfunction "IN-_3") (pintype "unspecified"))
    )
    (net (code "30") (name "Net-(USB1-CC1)") (class "Default")
      (node (ref "R2") (pin "1") (pinfunction "1_1") (pintype "input"))
      (node (ref "USB1") (pin "4") (pinfunction "CC1_4") (pintype "unspecified"))
    )
    (net (code "31") (name "Net-(USB1-CC2)") (class "Default")
      (node (ref "R1") (pin "1") (pinfunction "1_1") (pintype "input"))
      (node (ref "USB1") (pin "10") (pinfunction "CC2_10") (pintype "unspecified"))
    )
    (net (code "32") (name "VBUS") (class "Default")
      (node (ref "D1") (pin "2") (pinfunction "A_2") (pintype "unspecified"))
      (node (ref "Q2") (pin "1") (pinfunction "G_1") (pintype "unspecified"))
      (node (ref "R11") (pin "2") (pinfunction "2_2") (pintype "input"))
      (node (ref "R5") (pin "1") (pinfunction "1_1") (pintype "unspecified"))
      (node (ref "USB1") (pin "11") (pinfunction "VBUS_11") (pintype "unspecified"))
      (node (ref "USB1") (pin "2") (pinfunction "VBUS_2") (pintype "unspecified"))
    )
    (net (code "33") (name "VIN") (class "Default")
      (node (ref "C5") (pin "2") (pinfunction "2_2") (pintype "unspecified"))
      (node (ref "C6") (pin "2") (pinfunction "2_2") (pintype "unspecified"))
      (node (ref "D1") (pin "1") (pinfunction "K_1") (pintype "unspecified"))
      (node (ref "Q2") (pin "2") (pinfunction "S_2") (pintype "unspecified"))
      (node (ref "U2") (pin "1") (pinfunction "VIN_1") (pintype "unspecified"))
      (node (ref "U2") (pin "3") (pinfunction "CE_3") (pintype "unspecified"))
    )
    (net (code "34") (name "unconnected-(SCREW1-Pad1)") (class "Default")
      (node (ref "SCREW1") (pin "1") (pinfunction "1_1") (pintype "input+no_connect"))
    )
    (net (code "35") (name "unconnected-(SCREW2-Pad1)") (class "Default")
      (node (ref "SCREW2") (pin "1") (pinfunction "1_1") (pintype "input+no_connect"))
    )
    (net (code "36") (name "unconnected-(SCREW3-Pad1)") (class "Default")
      (node (ref "SCREW3") (pin "1") (pinfunction "1_1") (pintype "input+no_connect"))
    )
    (net (code "37") (name "unconnected-(SCREW4-Pad1)") (class "Default")
      (node (ref "SCREW4") (pin "1") (pinfunction "1_1") (pintype "input+no_connect"))
    )
    (net (code "38") (name "unconnected-(SW1-Pad1)") (class "Default")
      (node (ref "SW1") (pin "1") (pinfunction "1_1") (pintype "unspecified+no_connect"))
    )
    (net (code "39") (name "unconnected-(SW1-Pad2)") (class "Default")
      (node (ref "SW1") (pin "2") (pinfunction "2_2") (pintype "unspecified+no_connect"))
    )
    (net (code "40") (name "unconnected-(U2-NC-Pad4)") (class "Default")
      (node (ref "U2") (pin "4") (pinfunction "NC_4") (pintype "unspecified+no_connect"))
    )
    (net (code "41") (name "unconnected-(U3-RTS#-Pad4)") (class "Default")
      (node (ref "U3") (pin "4") (pinfunction "RTS#_4") (pintype "unspecified+no_connect"))
    )
    (net (code "42") (name "unconnected-(U4-PA1-Pad8)") (class "Default")
      (node (ref "U4") (pin "8") (pinfunction "PA1_8") (pintype "unspecified+no_connect"))
    )
    (net (code "43") (name "unconnected-(U4-PA4-Pad11)") (class "Default")
      (node (ref "U4") (pin "11") (pinfunction "PA4_11") (pintype "unspecified+no_connect"))
    )
    (net (code "44") (name "unconnected-(U4-PA5-Pad12)") (class "Default")
      (node (ref "U4") (pin "12") (pinfunction "PA5_12") (pintype "unspecified+no_connect"))
    )
    (net (code "45") (name "unconnected-(U4-PA6-Pad13)") (class "Default")
      (node (ref "U4") (pin "13") (pinfunction "PA6_13") (pintype "unspecified+no_connect"))
    )
    (net (code "46") (name "unconnected-(U4-PA7-Pad14)") (class "Default")
      (node (ref "U4") (pin "14") (pinfunction "PA7_14") (pintype "unspecified+no_connect"))
    )
    (net (code "47") (name "unconnected-(U4-PB3{slash}PB4{slash}PB5{slash}PB6-Pad20)") (class "Default")
      (node (ref "U4") (pin "20") (pinfunction "PB3/PB4/PB5/PB6_20") (pintype "unspecified+no_connect"))
    )
    (net (code "48") (name "unconnected-(USB1-SBU1-Pad9)") (class "Default")
      (node (ref "USB1") (pin "9") (pinfunction "SBU1_9") (pintype "unspecified+no_connect"))
    )
    (net (code "49") (name "unconnected-(USB1-SBU2-Pad3)") (class "Default")
      (node (ref "USB1") (pin "3") (pinfunction "SBU2_3") (pintype "unspecified+no_connect"))
    )
  )
)
